# ADC-RDC-IO.net
KiCad netlist of a schematic drawn in Altium Designer
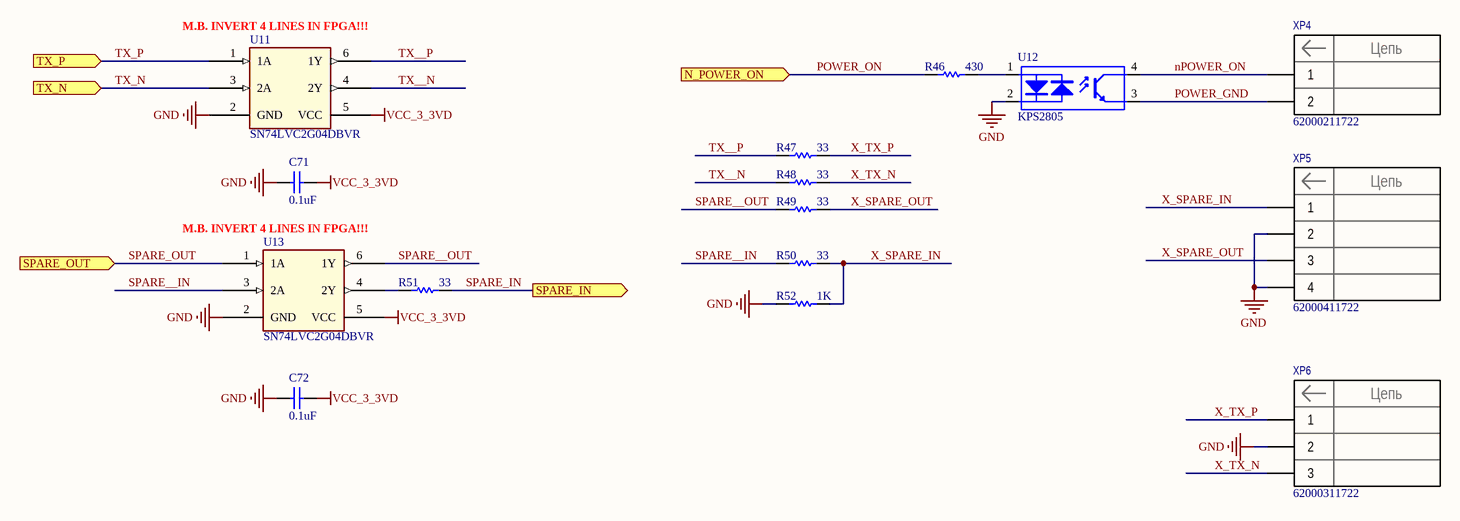
[diagram p0: ADC-RDC-IO.SchDoc]

(export (version "E")
  (design (tool "Eeschema 10.0.6"))
  (components
    (comp (ref "C71")
      (value "0.1uF")
      (footprint "C0603")
      (description "Capacitor, 2pin")
      (libsource (lib "GC500EM2") (part "Cap"))
    )
    (comp (ref "C72")
      (value "0.1uF")
      (footprint "C0603")
      (description "Capacitor, 2pin")
      (libsource (lib "GC500EM2") (part "Cap"))
    )
    (comp (ref "R46")
      (value "430")
      (footprint "R0603")
      (description "Resistor, 2pin")
      (libsource (lib "GC500EM2") (part "RES"))
    )
    (comp (ref "R47")
      (value "33")
      (footprint "R0603")
      (description "Resistor, 2pin")
      (libsource (lib "GC500EM2") (part "RES"))
    )
    (comp (ref "R48")
      (value "33")
      (footprint "R0603")
      (description "Resistor, 2pin")
      (libsource (lib "GC500EM2") (part "RES"))
    )
    (comp (ref "R49")
      (value "33")
      (footprint "R0603")
      (description "Resistor, 2pin")
      (libsource (lib "GC500EM2") (part "RES"))
    )
    (comp (ref "R50")
      (value "33")
      (footprint "R0603")
      (description "Resistor, 2pin")
      (libsource (lib "GC500EM2") (part "RES"))
    )
    (comp (ref "R51")
      (value "33")
      (footprint "R0603")
      (description "Resistor, 2pin")
      (libsource (lib "GC500EM2") (part "RES"))
    )
    (comp (ref "R52")
      (value "1K")
      (footprint "R0603")
      (description "Resistor, 2pin")
      (libsource (lib "GC500EM2") (part "RES"))
    )
    (comp (ref "U11")
      (value "SN74LVC2G04DBVR")
      (footprint "SOT23-6")
      (description "DUAL INVERTER GATE")
      (libsource (lib "GC500EM2") (part "SN74LVC2G04DBVR"))
    )
    (comp (ref "U12")
      (value "KPS2805")
      (footprint "SOP4")
      (description "Phototransistor Optocoupler, 4-Pin")
      (libsource (lib "GC500EM2") (part "KPS2805"))
    )
    (comp (ref "U13")
      (value "SN74LVC2G04DBVR")
      (footprint "SOT23-6")
      (description "DUAL INVERTER GATE")
      (libsource (lib "GC500EM2") (part "SN74LVC2G04DBVR"))
    )
    (comp (ref "XP4")
      (value "plug_62000211722_WR-WTB_2pin_horiz")
      (footprint "conP_WR-WTB_62000211722-2pin_P2000_60x76x48_L")
      (description "2.00mm Male Horizontal Shrouded Header WR-WTB")
      (fields
        (field (name "COMPONENT_NAME") "62000211722")
        (field (name "MANUFACTURER") "\"Wurth Elektronik\"")
      )
      (libsource (lib "Electromechanics") (part "plug_62000211722_WR-WTB_2pin_horiz"))
    )
    (comp (ref "XP5")
      (value "plug_62000411722_WR-WTB_4pin_horiz")
      (footprint "conP_WR-WTB_62000411722-4pin_P2000_100x76x48_L")
      (description "2.00mm Male Vertical Shrouded Header WR-WTB")
      (fields
        (field (name "COMPONENT_NAME") "62000411722")
        (field (name "MANUFACTURER") "\"Wurth Elektronik\"")
      )
      (libsource (lib "Electromechanics") (part "plug_62000411722_WR-WTB_4pin_horiz"))
    )
    (comp (ref "XP6")
      (value "plug_62000311722_WR-WTB_3pin_horiz")
      (footprint "conP_WR-WTB_62000311722-3pin_P2000_80x76x48_L")
      (description "2.00mm Male Vertical Shrouded Header WR-WTB")
      (fields
        (field (name "COMPONENT_NAME") "62000311722")
        (field (name "MANUFACTURER") "\"Wurth Elektronik\"")
      )
      (libsource (lib "Electromechanics") (part "plug_62000311722_WR-WTB_3pin_horiz"))
    )
  )
  (nets
    (net (code "1") (name "/POWER_GND") (class "Default")
      (node (ref "U12") (pin "3") (pinfunction "E_3") (pintype "passive"))
      (node (ref "XP4") (pin "2") (pinfunction "2_2") (pintype "passive"))
    )
    (net (code "2") (name "/POWER_ON") (class "Default")
      (node (ref "R46") (pin "1") (pinfunction "1_1") (pintype "passive"))
    )
    (net (code "3") (name "/SPARE_IN") (class "Default")
      (node (ref "R51") (pin "2") (pinfunction "2_2") (pintype "passive"))
    )
    (net (code "4") (name "/SPARE_OUT") (class "Default")
      (node (ref "U13") (pin "1") (pinfunction "1A_1") (pintype "input"))
    )
    (net (code "5") (name "/SPARE__IN") (class "Default")
      (node (ref "R50") (pin "1") (pinfunction "1_1") (pintype "passive"))
      (node (ref "U13") (pin "3") (pinfunction "2A_3") (pintype "input"))
    )
    (net (code "6") (name "/SPARE__OUT") (class "Default")
      (node (ref "R49") (pin "1") (pinfunction "1_1") (pintype "passive"))
      (node (ref "U13") (pin "6") (pinfunction "1Y_6") (pintype "output"))
    )
    (net (code "7") (name "/TX_N") (class "Default")
      (node (ref "U11") (pin "3") (pinfunction "2A_3") (pintype "input"))
    )
    (net (code "8") (name "/TX_P") (class "Default")
      (node (ref "U11") (pin "1") (pinfunction "1A_1") (pintype "input"))
    )
    (net (code "9") (name "/TX__N") (class "Default")
      (node (ref "R48") (pin "1") (pinfunction "1_1") (pintype "passive"))
      (node (ref "U11") (pin "4") (pinfunction "2Y_4") (pintype "output"))
    )
    (net (code "10") (name "/TX__P") (class "Default")
      (node (ref "R47") (pin "1") (pinfunction "1_1") (pintype "passive"))
      (node (ref "U11") (pin "6") (pinfunction "1Y_6") (pintype "output"))
    )
    (net (code "11") (name "/X_SPARE_IN") (class "Default")
      (node (ref "R50") (pin "2") (pinfunction "2_2") (pintype "passive"))
      (node (ref "R52") (pin "2") (pinfunction "2_2") (pintype "passive"))
      (node (ref "XP5") (pin "1") (pinfunction "1_1") (pintype "passive"))
    )
    (net (code "12") (name "/X_SPARE_OUT") (class "Default")
      (node (ref "R49") (pin "2") (pinfunction "2_2") (pintype "passive"))
      (node (ref "XP5") (pin "3") (pinfunction "3_3") (pintype "passive"))
    )
    (net (code "13") (name "/X_TX_N") (class "Default")
      (node (ref "R48") (pin "2") (pinfunction "2_2") (pintype "passive"))
      (node (ref "XP6") (pin "3") (pinfunction "3_3") (pintype "passive"))
    )
    (net (code "14") (name "/X_TX_P") (class "Default")
      (node (ref "R47") (pin "2") (pinfunction "2_2") (pintype "passive"))
      (node (ref "XP6") (pin "1") (pinfunction "1_1") (pintype "passive"))
    )
    (net (code "16") (name "/nPOWER_ON") (class "Default")
      (node (ref "U12") (pin "4") (pinfunction "C_4") (pintype "passive"))
      (node (ref "XP4") (pin "1") (pinfunction "1_1") (pintype "passive"))
    )
    (net (code "17") (name "GND") (class "Default")
      (node (ref "C71") (pin "1") (pinfunction "1_1") (pintype "passive"))
      (node (ref "C72") (pin "1") (pinfunction "1_1") (pintype "passive"))
      (node (ref "R52") (pin "1") (pinfunction "1_1") (pintype "passive"))
      (node (ref "U11") (pin "2") (pinfunction "GND_2") (pintype "power_in"))
      (node (ref "U12") (pin "2") (pinfunction "K_2") (pintype "passive"))
      (node (ref "U13") (pin "2") (pinfunction "GND_2") (pintype "power_in"))
      (node (ref "XP5") (pin "2") (pinfunction "2_2") (pintype "passive"))
      (node (ref "XP5") (pin "4") (pinfunction "4_4") (pintype "passive"))
      (node (ref "XP6") (pin "2") (pinfunction "2_2") (pintype "passive"))
    )
    (net (code "18") (name "Net-(U12-A)") (class "Default")
      (node (ref "R46") (pin "2") (pinfunction "2_2") (pintype "passive"))
      (node (ref "U12") (pin "1") (pinfunction "A_1") (pintype "passive"))
    )
    (net (code "19") (name "Net-(U13-2Y)") (class "Default")
      (node (ref "R51") (pin "1") (pinfunction "1_1") (pintype "passive"))
      (node (ref "U13") (pin "4") (pinfunction "2Y_4") (pintype "output"))
    )
    (net (code "20") (name "VCC_3_3VD") (class "Default")
      (node (ref "C71") (pin "2") (pinfunction "2_2") (pintype "passive"))
      (node (ref "C72") (pin "2") (pinfunction "2_2") (pintype "passive"))
      (node (ref "U11") (pin "5") (pinfunction "VCC_5") (pintype "power_in"))
      (node (ref "U13") (pin "5") (pinfunction "VCC_5") (pintype "power_in"))
    )
  )
)
